# oddspi.net
KiCad netlist of a schematic drawn in EAGLE
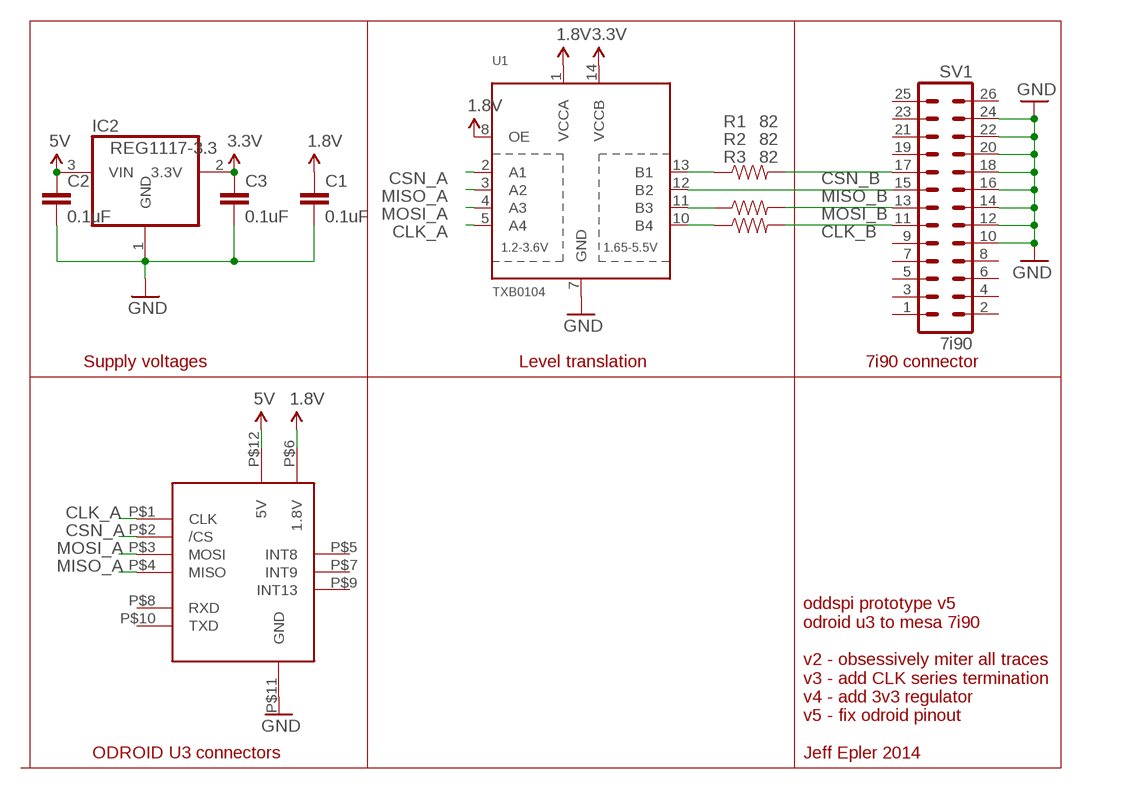
[diagram p0: schematic, sheet 1]

(export (version "E")
  (design (tool "Eeschema 10.0.6"))
  (components
    (comp (ref "C1")
      (value "0.1uF")
      (footprint "eagle-import:0603-CAP")
      (libsource (lib "eagle-import") (part "0.1UF-25V(+80/-20%)(0603)"))
    )
    (comp (ref "C2")
      (value "0.1uF")
      (footprint "eagle-import:0603-CAP")
      (libsource (lib "eagle-import") (part "0.1UF-25V(+80/-20%)(0603)"))
    )
    (comp (ref "C3")
      (value "0.1uF")
      (footprint "eagle-import:0603-CAP")
      (libsource (lib "eagle-import") (part "0.1UF-25V(+80/-20%)(0603)"))
    )
    (comp (ref "IC2")
      (value "REG1117-3.3")
      (footprint "eagle-import:SOT223")
      (fields (field (name "MPN") "REG1117"))
      (libsource (lib "eagle-import") (part "REG1117-3.3"))
    )
    (comp (ref "R1")
      (value "82")
      (footprint "eagle-import:0603-RES")
      (libsource (lib "eagle-import") (part "RESISTOR0603-RES"))
    )
    (comp (ref "R2")
      (value "82")
      (footprint "eagle-import:0603-RES")
      (libsource (lib "eagle-import") (part "RESISTOR0603-RES"))
    )
    (comp (ref "R3")
      (value "82")
      (footprint "eagle-import:0603-RES")
      (libsource (lib "eagle-import") (part "RESISTOR0603-RES"))
    )
    (comp (ref "SV1")
      (value "7i90")
      (footprint "eagle-import:ML26")
      (libsource (lib "eagle-import") (part "ML26"))
    )
    (comp (ref "U$4")
      (value "ODROID-U3")
      (footprint "eagle-import:U3V05")
      (libsource (lib "eagle-import") (part "ODROID-U3"))
    )
    (comp (ref "U1")
      (value "TXB0104")
      (footprint "eagle-import:SO14")
      (libsource (lib "eagle-import") (part "TXB0104PWRSOIC14"))
    )
  )
  (nets
    (net (code "1") (name "/CLK_A") (class "Default")
      (node (ref "U$4") (pin "P$1") (pinfunction "CLK_P$1") (pintype "bidirectional"))
      (node (ref "U1") (pin "5") (pinfunction "A4_5") (pintype "bidirectional"))
    )
    (net (code "2") (name "/CLK_B") (class "Default")
      (node (ref "R1") (pin "2") (pinfunction "2_2") (pintype "passive"))
      (node (ref "SV1") (pin "11") (pinfunction "11_11") (pintype "passive"))
    )
    (net (code "3") (name "/CSN_A") (class "Default")
      (node (ref "U$4") (pin "P$2") (pinfunction "/CS_P$2") (pintype "bidirectional"))
      (node (ref "U1") (pin "2") (pinfunction "A1_2") (pintype "bidirectional"))
    )
    (net (code "4") (name "/CSN_B") (class "Default")
      (node (ref "R3") (pin "2") (pinfunction "2_2") (pintype "passive"))
      (node (ref "SV1") (pin "17") (pinfunction "17_17") (pintype "passive"))
    )
    (net (code "5") (name "/MISO_A") (class "Default")
      (node (ref "U$4") (pin "P$4") (pinfunction "MISO_P$4") (pintype "input"))
      (node (ref "U1") (pin "3") (pinfunction "A2_3") (pintype "bidirectional"))
    )
    (net (code "6") (name "/MISO_B") (class "Default")
      (node (ref "SV1") (pin "15") (pinfunction "15_15") (pintype "passive"))
      (node (ref "U1") (pin "12") (pinfunction "B2_12") (pintype "bidirectional"))
    )
    (net (code "7") (name "/MOSI_A") (class "Default")
      (node (ref "U$4") (pin "P$3") (pinfunction "MOSI_P$3") (pintype "output"))
      (node (ref "U1") (pin "4") (pinfunction "A3_4") (pintype "bidirectional"))
    )
    (net (code "8") (name "/MOSI_B") (class "Default")
      (node (ref "R2") (pin "2") (pinfunction "2_2") (pintype "passive"))
      (node (ref "SV1") (pin "13") (pinfunction "13_13") (pintype "passive"))
    )
    (net (code "9") (name "1.8V") (class "Default")
      (node (ref "C1") (pin "1") (pinfunction "1_1") (pintype "passive"))
      (node (ref "U$4") (pin "P$6") (pinfunction "1.8V_P$6") (pintype "power_in"))
      (node (ref "U1") (pin "1") (pinfunction "VCCA_1") (pintype "bidirectional"))
      (node (ref "U1") (pin "8") (pinfunction "OE_8") (pintype "bidirectional"))
    )
    (net (code "10") (name "3.3V") (class "Default")
      (node (ref "C3") (pin "1") (pinfunction "1_1") (pintype "passive"))
      (node (ref "IC2") (pin "2") (pinfunction "3.3V_2") (pintype "power_in"))
      (node (ref "U1") (pin "14") (pinfunction "VCCB_14") (pintype "bidirectional"))
    )
    (net (code "11") (name "5V") (class "Default")
      (node (ref "C2") (pin "1") (pinfunction "1_1") (pintype "passive"))
      (node (ref "IC2") (pin "3") (pinfunction "VIN_3") (pintype "input"))
      (node (ref "U$4") (pin "P$12") (pinfunction "5V_P$12") (pintype "power_in"))
    )
    (net (code "12") (name "GND") (class "Default")
      (node (ref "C1") (pin "2") (pinfunction "2_2") (pintype "passive"))
      (node (ref "C2") (pin "2") (pinfunction "2_2") (pintype "passive"))
      (node (ref "C3") (pin "2") (pinfunction "2_2") (pintype "passive"))
      (node (ref "IC2") (pin "1") (pinfunction "GND_1") (pintype "power_in"))
      (node (ref "SV1") (pin "10") (pinfunction "10_10") (pintype "passive"))
      (node (ref "SV1") (pin "12") (pinfunction "12_12") (pintype "passive"))
      (node (ref "SV1") (pin "14") (pinfunction "14_14") (pintype "passive"))
      (node (ref "SV1") (pin "16") (pinfunction "16_16") (pintype "passive"))
      (node (ref "SV1") (pin "18") (pinfunction "18_18") (pintype "passive"))
      (node (ref "SV1") (pin "20") (pinfunction "20_20") (pintype "passive"))
      (node (ref "SV1") (pin "22") (pinfunction "22_22") (pintype "passive"))
      (node (ref "SV1") (pin "24") (pinfunction "24_24") (pintype "passive"))
      (node (ref "U$4") (pin "P$11") (pinfunction "GND_P$11") (pintype "power_in"))
      (node (ref "U1") (pin "7") (pinfunction "GND_7") (pintype "bidirectional"))
    )
    (net (code "13") (name "Net-(U1-B1)") (class "Default")
      (node (ref "R3") (pin "1") (pinfunction "1_1") (pintype "passive"))
      (node (ref "U1") (pin "13") (pinfunction "B1_13") (pintype "bidirectional"))
    )
    (net (code "14") (name "Net-(U1-B3)") (class "Default")
      (node (ref "R2") (pin "1") (pinfunction "1_1") (pintype "passive"))
      (node (ref "U1") (pin "11") (pinfunction "B3_11") (pintype "bidirectional"))
    )
    (net (code "15") (name "Net-(U1-B4)") (class "Default")
      (node (ref "R1") (pin "1") (pinfunction "1_1") (pintype "passive"))
      (node (ref "U1") (pin "10") (pinfunction "B4_10") (pintype "bidirectional"))
    )
    (net (code "16") (name "unconnected-(SV1-Pad1)") (class "Default")
      (node (ref "SV1") (pin "1") (pinfunction "1_1") (pintype "passive"))
    )
    (net (code "17") (name "unconnected-(SV1-Pad2)") (class "Default")
      (node (ref "SV1") (pin "2") (pinfunction "2_2") (pintype "passive"))
    )
    (net (code "18") (name "unconnected-(SV1-Pad3)") (class "Default")
      (node (ref "SV1") (pin "3") (pinfunction "3_3") (pintype "passive"))
    )
    (net (code "19") (name "unconnected-(SV1-Pad4)") (class "Default")
      (node (ref "SV1") (pin "4") (pinfunction "4_4") (pintype "passive"))
    )
    (net (code "20") (name "unconnected-(SV1-Pad5)") (class "Default")
      (node (ref "SV1") (pin "5") (pinfunction "5_5") (pintype "passive"))
    )
    (net (code "21") (name "unconnected-(SV1-Pad6)") (class "Default")
      (node (ref "SV1") (pin "6") (pinfunction "6_6") (pintype "passive"))
    )
    (net (code "22") (name "unconnected-(SV1-Pad7)") (class "Default")
      (node (ref "SV1") (pin "7") (pinfunction "7_7") (pintype "passive"))
    )
    (net (code "23") (name "unconnected-(SV1-Pad8)") (class "Default")
      (node (ref "SV1") (pin "8") (pinfunction "8_8") (pintype "passive"))
    )
    (net (code "24") (name "unconnected-(SV1-Pad9)") (class "Default")
      (node (ref "SV1") (pin "9") (pinfunction "9_9") (pintype "passive"))
    )
    (net (code "25") (name "unconnected-(SV1-Pad19)") (class "Default")
      (node (ref "SV1") (pin "19") (pinfunction "19_19") (pintype "passive"))
    )
    (net (code "26") (name "unconnected-(SV1-Pad21)") (class "Default")
      (node (ref "SV1") (pin "21") (pinfunction "21_21") (pintype "passive"))
    )
    (net (code "27") (name "unconnected-(SV1-Pad23)") (class "Default")
      (node (ref "SV1") (pin "23") (pinfunction "23_23") (pintype "passive"))
    )
    (net (code "28") (name "unconnected-(SV1-Pad25)") (class "Default")
      (node (ref "SV1") (pin "25") (pinfunction "25_25") (pintype "passive"))
    )
    (net (code "29") (name "unconnected-(SV1-Pad26)") (class "Default")
      (node (ref "SV1") (pin "26") (pinfunction "26_26") (pintype "passive"))
    )
    (net (code "30") (name "unconnected-(U$4-INT8-PadP$5)") (class "Default")
      (node (ref "U$4") (pin "P$5") (pinfunction "INT8_P$5") (pintype "bidirectional"))
    )
    (net (code "31") (name "unconnected-(U$4-INT9-PadP$7)") (class "Default")
      (node (ref "U$4") (pin "P$7") (pinfunction "INT9_P$7") (pintype "bidirectional"))
    )
    (net (code "32") (name "unconnected-(U$4-INT13-PadP$9)") (class "Default")
      (node (ref "U$4") (pin "P$9") (pinfunction "INT13_P$9") (pintype "bidirectional"))
    )
    (net (code "33") (name "unconnected-(U$4-RXD-PadP$8)") (class "Default")
      (node (ref "U$4") (pin "P$8") (pinfunction "RXD_P$8") (pintype "bidirectional"))
    )
    (net (code "34") (name "unconnected-(U$4-TXD-PadP$10)") (class "Default")
      (node (ref "U$4") (pin "P$10") (pinfunction "TXD_P$10") (pintype "bidirectional"))
    )
  )
)
